# design_schematic.net
KiCad netlist of a schematic drawn in EasyEDA
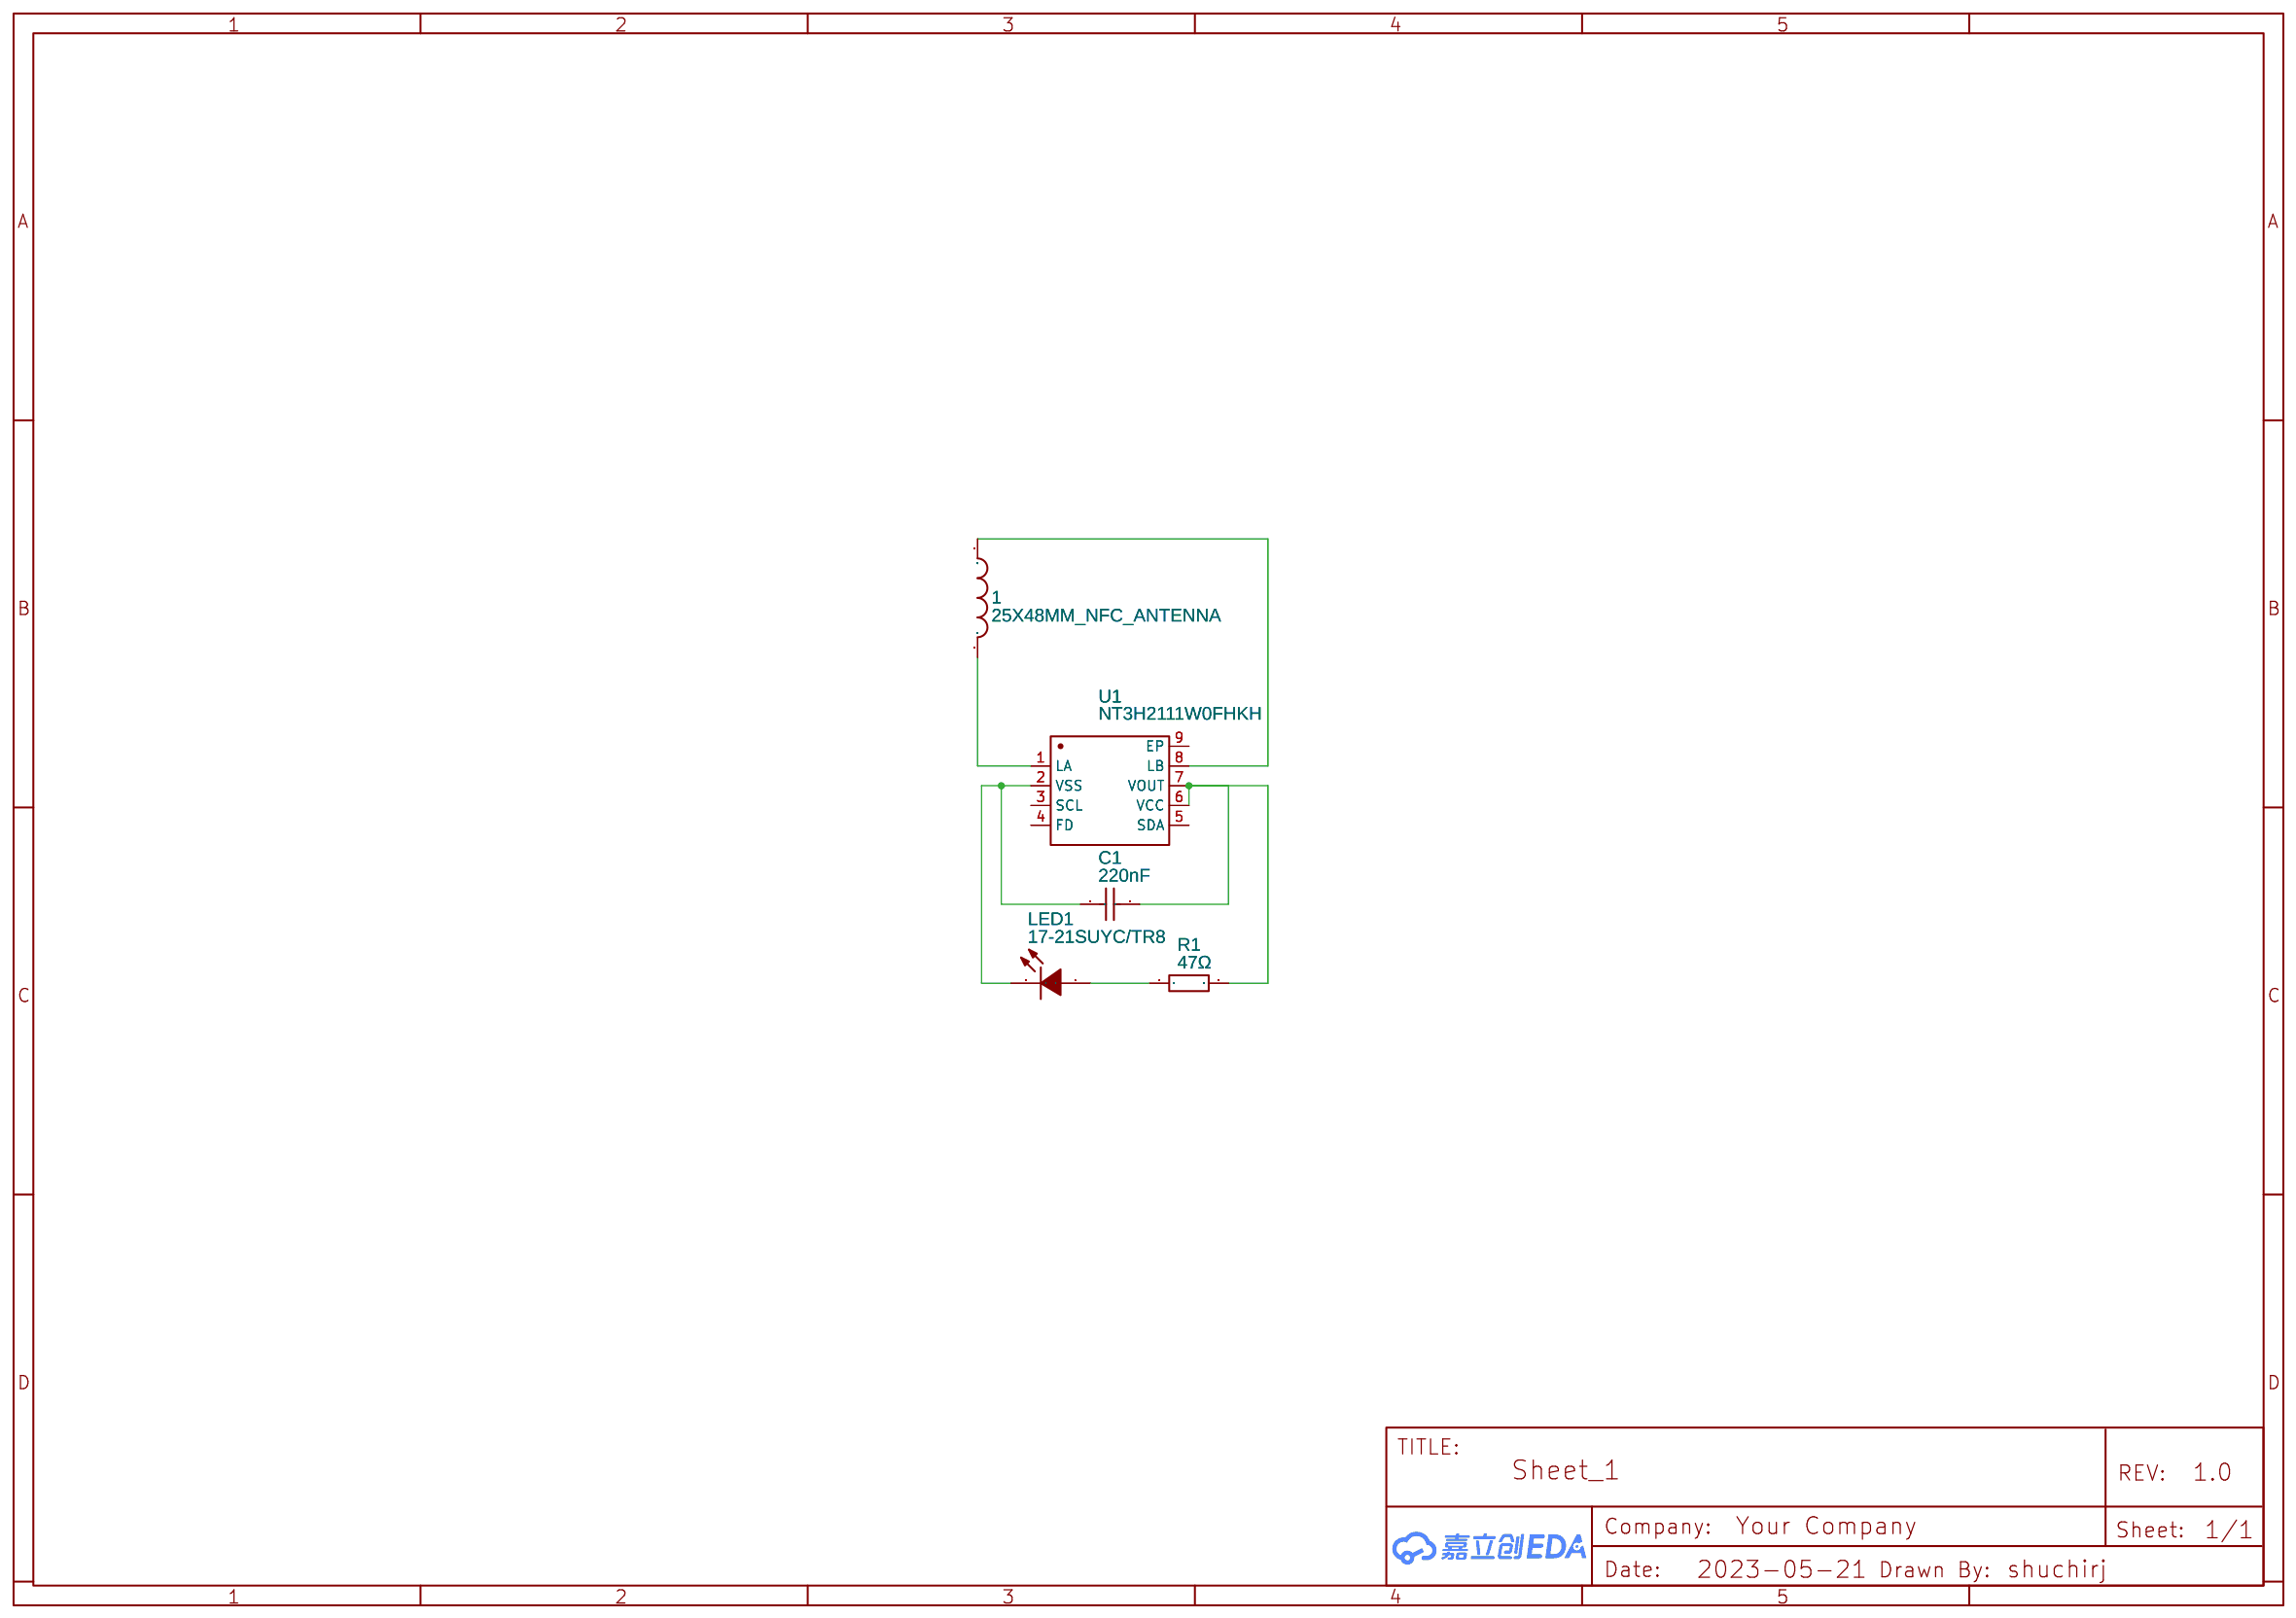
[diagram p0: schematic sheet]

(export (version "E")
  (design (tool "Eeschema 10.0.6"))
  (components
    (comp (ref "1") (value "25X48MM_NFC_ANTENNA") (libsource (lib "") (part "25X48MM_NFC_ANTENNA")))
    (comp (ref "C1")
      (value "220nF")
      (fields
        (field (name "BOM_Manufacturer Part") "CL10B224KA8NNNC")
        (field (name "BOM_Supplier Part") "C21120")
      )
      (libsource (lib "") (part "CL10B224KA8NNNC"))
    )
    (comp (ref "LED1")
      (value "17-21SUYC/TR8")
      (fields (field (name "BOM_Manufacturer Part") "KT-0805黄灯") (field (name "BOM_Supplier Part") "C2296"))
      (libsource (lib "") (part "17-21SUYC/TR8"))
    )
    (comp (ref "R1")
      (value "47Ω")
      (fields
        (field (name "BOM_Manufacturer Part") "0603WAF470JT5E")
        (field (name "BOM_Supplier Part") "C23182")
      )
      (libsource (lib "") (part "0603WAF470JT5E"))
    )
    (comp (ref "U1")
      (value "NT3H2111W0FHKH")
      (fields (field (name "BOM_Supplier Part") "C710403"))
      (libsource (lib "") (part "NT3H2111W0FHKH"))
    )
  )
  (nets
    (net (code "1") (name "Net-(LED1-+)") (class "Default")
      (node (ref "LED1") (pin "1") (pinfunction "+_1") (pintype "unspecified"))
      (node (ref "R1") (pin "1") (pinfunction "1_1") (pintype "input"))
    )
    (net (code "2") (name "Net-(LED1--)") (class "Default")
      (node (ref "C1") (pin "1") (pinfunction "1_1") (pintype "input"))
      (node (ref "LED1") (pin "2") (pinfunction "-_2") (pintype "unspecified"))
      (node (ref "U1") (pin "2") (pinfunction "VSS_2") (pintype "unspecified"))
    )
    (net (code "3") (name "Net-(U1-LA)") (class "Default")
      (node (ref "1") (pin "P$2") (pinfunction "P$2_P$2") (pintype "bidirectional"))
      (node (ref "U1") (pin "1") (pinfunction "LA_1") (pintype "unspecified"))
    )
    (net (code "4") (name "Net-(U1-LB)") (class "Default")
      (node (ref "1") (pin "P$1") (pinfunction "P$1_P$1") (pintype "bidirectional"))
      (node (ref "U1") (pin "8") (pinfunction "LB_8") (pintype "unspecified"))
    )
    (net (code "5") (name "Net-(U1-VCC)") (class "Default")
      (node (ref "C1") (pin "2") (pinfunction "2_2") (pintype "input"))
      (node (ref "R1") (pin "2") (pinfunction "2_2") (pintype "input"))
      (node (ref "U1") (pin "6") (pinfunction "VCC_6") (pintype "unspecified"))
      (node (ref "U1") (pin "7") (pinfunction "VOUT_7") (pintype "unspecified"))
    )
    (net (code "6") (name "unconnected-(U1-EP-Pad9)") (class "Default")
      (node (ref "U1") (pin "9") (pinfunction "EP_9") (pintype "unspecified"))
    )
    (net (code "7") (name "unconnected-(U1-FD-Pad4)") (class "Default")
      (node (ref "U1") (pin "4") (pinfunction "FD_4") (pintype "unspecified"))
    )
    (net (code "8") (name "unconnected-(U1-SCL-Pad3)") (class "Default")
      (node (ref "U1") (pin "3") (pinfunction "SCL_3") (pintype "unspecified"))
    )
    (net (code "9") (name "unconnected-(U1-SDA-Pad5)") (class "Default")
      (node (ref "U1") (pin "5") (pinfunction "SDA_5") (pintype "unspecified"))
    )
  )
)
